# Display_Buttons.net
KiCad netlist of a schematic drawn in Altium Designer
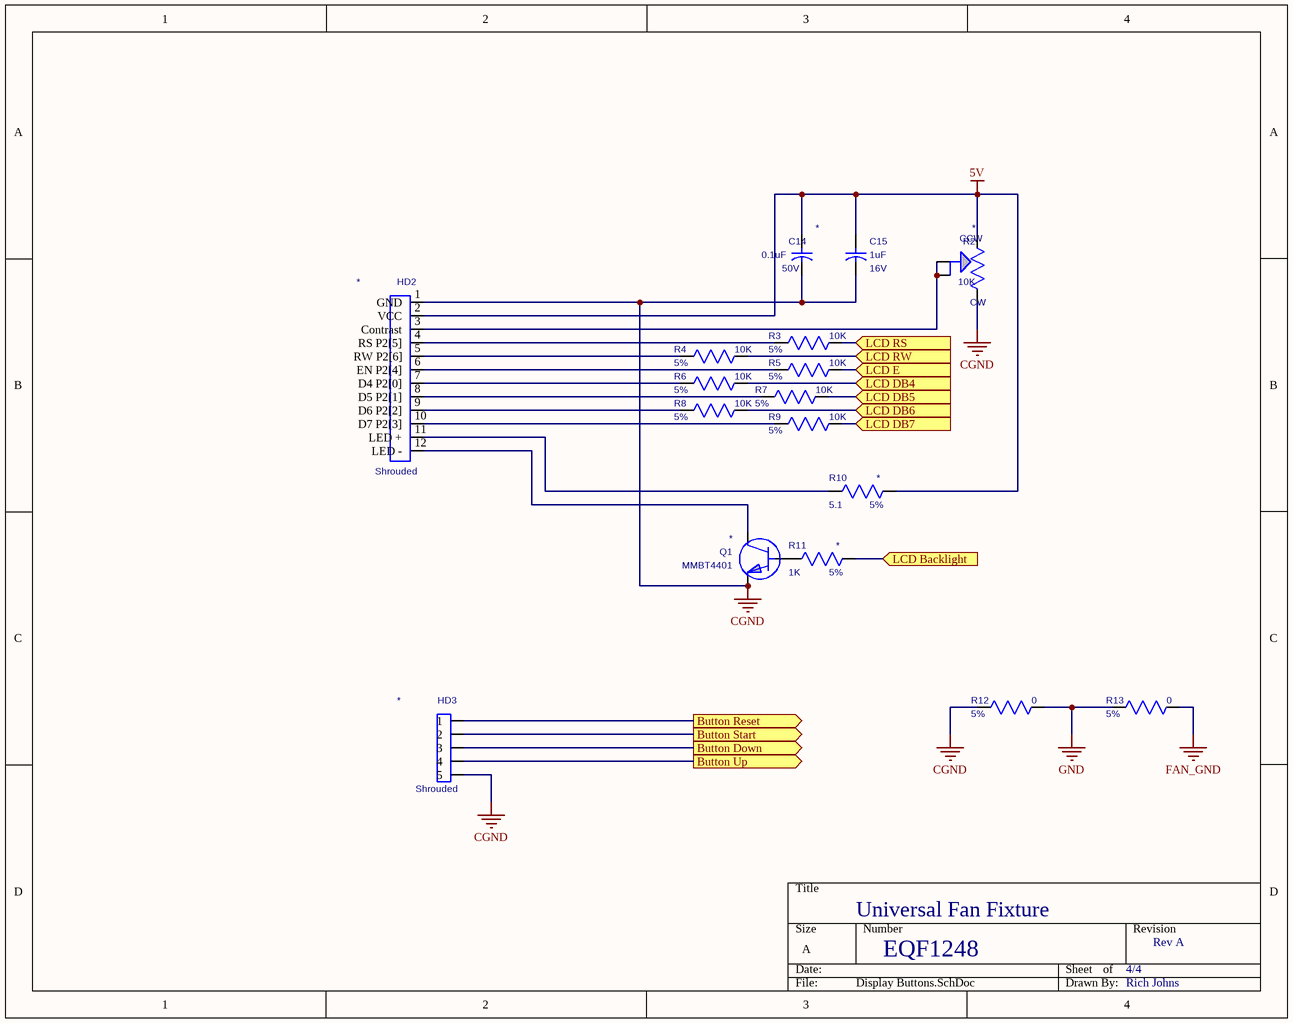
[diagram p0: Display Buttons.SchDoc]

(export (version "E")
  (design (tool "Eeschema 10.0.6"))
  (components
    (comp (ref "C14")
      (value "0.1uF")
      (footprint "0603")
      (fields
        (field (name "DNS") "*")
        (field (name "VOLTAGE") "50V")
        (field (name "TOLERANCE") "+/- 20%")
        (field (name "Comment") "CAP_NON_POLAR_SMT")
        (field (name "CHECKEDBY") "Sam Rhoufiry")
        (field (name "CREATEDBY") "Mike Tyger")
        (field (name "LASTUPDATEDBY") "Mike Tyger")
      )
      (libsource (lib "bome") (part "CAP_NON_POLAR_SMT"))
    )
    (comp (ref "C15")
      (value "1uF")
      (footprint "0603")
      (fields
        (field (name "TOLERANCE") "+/- 10%")
        (field (name "VOLTAGE") "16V")
        (field (name "Comment") "1.0uF_0603_16V")
        (field (name "CHECKEDBY") "gdeguzman")
        (field (name "LASTUPDATEDBY") "Rui Zhang")
      )
      (libsource (lib "bome") (part "1.0uF_0603_16V"))
    )
    (comp (ref "HD2")
      (value "HDR12PIN100SHRD")
      (footprint "HDR12PIN100SHRD")
      (description "Header, 0.1 in., 12 pins Pins, Shrouded, AMP: 1-64486-2")
      (fields
        (field (name "DNS") "*")
        (field (name "HEADERTYPE") "Shrouded")
        (field (name "CHECKEDBY") "Michael Angeli")
      )
      (libsource (lib "bome") (part "HDR12PIN100SHRD"))
    )
    (comp (ref "HD3")
      (value "HDR5PIN100SHRD")
      (footprint "HDR5PIN100SHRD")
      (description "Header, 0.100 in., 5 pin Pins, Shrouded, AMP: 644486-5")
      (fields
        (field (name "DNS") "*")
        (field (name "HEADERTYPE") "Shrouded")
        (field (name "CHECKEDBY") "Michael Angeli")
      )
      (libsource (lib "bome") (part "HDR5PIN100SHRD"))
    )
    (comp (ref "Q1")
      (value "MMBT4401")
      (footprint "SOT23-3")
      (description "Transistor, MMBT4401, 40V, SOT23-3, 500mA, NPN, Transistor, On Semi: MMBT4401LT1")
      (fields
        (field (name "DNS") "*")
        (field (name "VOLTAGE") "40V")
        (field (name "Comment") "NPN_TRANSISTOR")
        (field (name "CHECKEDBY") "gdeguzman")
        (field (name "CREATEDBY") "Mike Tyger")
        (field (name "LASTUPDATEDBY") "Mike Tyger")
      )
      (libsource (lib "bome") (part "NPN_TRANSISTOR"))
    )
    (comp (ref "R2")
      (value "10K")
      (footprint "6MM POT")
      (description "Resistor, 10K, Carbon, 20%, 0.2 in X 0.1 in or 0.2 in X 0.2 in, 0.1W, Panasonic: EVN-D8AA03B14")
      (fields
        (field (name "TOLERANCE") "20%")
        (field (name "DNS") "*")
        (field (name "Comment") "POT 6MM 10K")
        (field (name "CHECKEDBY") "B. Lyon")
      )
      (libsource (lib "bome") (part "POT 6MM 10K"))
    )
    (comp (ref "R3")
      (value "10K")
      (footprint "0603")
      (description "Resistor, 10K, ThickFilm, 5%, 0603, 1/10W, 2, Any")
      (fields
        (field (name "TOLERANCE") "5%")
        (field (name "Comment") "Resistor_0603_5%")
        (field (name "CHECKEDBY") "Joe Diffie")
        (field (name "LASTUPDATEDBY") "Rui Zhang")
      )
      (libsource (lib "bome") (part "Resistor_0603_5%"))
    )
    (comp (ref "R4")
      (value "10K")
      (footprint "0603")
      (description "Resistor, 10K, ThickFilm, 5%, 0603, 1/10W, 2, Any")
      (fields
        (field (name "TOLERANCE") "5%")
        (field (name "Comment") "Resistor_0603_5%")
        (field (name "CHECKEDBY") "Joe Diffie")
        (field (name "LASTUPDATEDBY") "Rui Zhang")
      )
      (libsource (lib "bome") (part "Resistor_0603_5%"))
    )
    (comp (ref "R5")
      (value "10K")
      (footprint "0603")
      (description "Resistor, 10K, ThickFilm, 5%, 0603, 1/10W, 2, Any")
      (fields
        (field (name "TOLERANCE") "5%")
        (field (name "Comment") "Resistor_0603_5%")
        (field (name "CHECKEDBY") "Joe Diffie")
        (field (name "LASTUPDATEDBY") "Rui Zhang")
      )
      (libsource (lib "bome") (part "Resistor_0603_5%"))
    )
    (comp (ref "R6")
      (value "10K")
      (footprint "0603")
      (description "Resistor, 10K, ThickFilm, 5%, 0603, 1/10W, 2, Any")
      (fields
        (field (name "TOLERANCE") "5%")
        (field (name "Comment") "Resistor_0603_5%")
        (field (name "CHECKEDBY") "Joe Diffie")
        (field (name "LASTUPDATEDBY") "Rui Zhang")
      )
      (libsource (lib "bome") (part "Resistor_0603_5%"))
    )
    (comp (ref "R7")
      (value "10K")
      (footprint "0603")
      (description "Resistor, 10K, ThickFilm, 5%, 0603, 1/10W, 2, Any")
      (fields
        (field (name "TOLERANCE") "5%")
        (field (name "Comment") "Resistor_0603_5%")
        (field (name "CHECKEDBY") "Joe Diffie")
        (field (name "LASTUPDATEDBY") "Rui Zhang")
      )
      (libsource (lib "bome") (part "Resistor_0603_5%"))
    )
    (comp (ref "R8")
      (value "10K")
      (footprint "0603")
      (description "Resistor, 10K, ThickFilm, 5%, 0603, 1/10W, 2, Any")
      (fields
        (field (name "TOLERANCE") "5%")
        (field (name "Comment") "Resistor_0603_5%")
        (field (name "CHECKEDBY") "Joe Diffie")
        (field (name "LASTUPDATEDBY") "Rui Zhang")
      )
      (libsource (lib "bome") (part "Resistor_0603_5%"))
    )
    (comp (ref "R9")
      (value "10K")
      (footprint "0603")
      (description "Resistor, 10K, ThickFilm, 5%, 0603, 1/10W, 2, Any")
      (fields
        (field (name "TOLERANCE") "5%")
        (field (name "Comment") "Resistor_0603_5%")
        (field (name "CHECKEDBY") "Joe Diffie")
        (field (name "LASTUPDATEDBY") "Rui Zhang")
      )
      (libsource (lib "bome") (part "Resistor_0603_5%"))
    )
    (comp (ref "R10")
      (value "5.1")
      (footprint "RC0603REFLOW-IPC")
      (description "Resistor, 5.1, ThickFilm, 5%, 0603, 1/10W, Any")
      (fields
        (field (name "DNS") "*")
        (field (name "TOLERANCE") "5%")
        (field (name "Comment") "R0603REFLOW_5%")
        (field (name "CHECKEDBY") "Michael Angeli")
      )
      (libsource (lib "bome") (part "R0603REFLOW_5%"))
    )
    (comp (ref "R11")
      (value "1K")
      (footprint "RC0603REFLOW-IPC")
      (description "Resistor, 1K, ThickFilm, 5%, 0603, 1/10W, Any")
      (fields
        (field (name "DNS") "*")
        (field (name "TOLERANCE") "5%")
        (field (name "Comment") "R0603REFLOW_5%")
        (field (name "CHECKEDBY") "Michael Angeli")
      )
      (libsource (lib "bome") (part "R0603REFLOW_5%"))
    )
    (comp (ref "R12")
      (value "0")
      (footprint "0603")
      (description "Resistor, 0, ThickFilm, 5%, 0603, 1/10W, 2, Any")
      (fields
        (field (name "TOLERANCE") "5%")
        (field (name "Comment") "Resistor_0603_5%")
        (field (name "CHECKEDBY") "Joe Diffie")
        (field (name "LASTUPDATEDBY") "Rui Zhang")
      )
      (libsource (lib "bome") (part "Resistor_0603_5%"))
    )
    (comp (ref "R13")
      (value "0")
      (footprint "0603")
      (description "Resistor, 0, ThickFilm, 5%, 0603, 1/10W, 2, Any")
      (fields
        (field (name "TOLERANCE") "5%")
        (field (name "Comment") "Resistor_0603_5%")
        (field (name "CHECKEDBY") "Joe Diffie")
        (field (name "LASTUPDATEDBY") "Rui Zhang")
      )
      (libsource (lib "bome") (part "Resistor_0603_5%"))
    )
  )
  (nets
    (net (code "1") (name "/Button Down") (class "Default")
      (node (ref "HD3") (pin "3") (pinfunction "3_3") (pintype "passive"))
    )
    (net (code "2") (name "/Button Reset") (class "Default")
      (node (ref "HD3") (pin "1") (pinfunction "1_1") (pintype "passive"))
    )
    (net (code "3") (name "/Button Start") (class "Default")
      (node (ref "HD3") (pin "2") (pinfunction "2_2") (pintype "passive"))
    )
    (net (code "4") (name "/Button Up") (class "Default")
      (node (ref "HD3") (pin "4") (pinfunction "4_4") (pintype "passive"))
    )
    (net (code "5") (name "/LCD Backlight") (class "Default")
      (node (ref "R11") (pin "1") (pinfunction "pin1_1") (pintype "passive"))
    )
    (net (code "6") (name "/LCD DB4") (class "Default")
      (node (ref "R6") (pin "1") (pinfunction "pin1_1") (pintype "passive"))
    )
    (net (code "7") (name "/LCD DB5") (class "Default")
      (node (ref "R7") (pin "1") (pinfunction "pin1_1") (pintype "passive"))
    )
    (net (code "8") (name "/LCD DB6") (class "Default")
      (node (ref "R8") (pin "1") (pinfunction "pin1_1") (pintype "passive"))
    )
    (net (code "9") (name "/LCD DB7") (class "Default")
      (node (ref "R9") (pin "1") (pinfunction "pin1_1") (pintype "passive"))
    )
    (net (code "10") (name "/LCD E") (class "Default")
      (node (ref "R5") (pin "1") (pinfunction "pin1_1") (pintype "passive"))
    )
    (net (code "11") (name "/LCD RS") (class "Default")
      (node (ref "R3") (pin "1") (pinfunction "pin1_1") (pintype "passive"))
    )
    (net (code "12") (name "/LCD RW") (class "Default")
      (node (ref "R4") (pin "1") (pinfunction "pin1_1") (pintype "passive"))
    )
    (net (code "13") (name "5V") (class "Default")
      (node (ref "C14") (pin "1") (pinfunction "pin1_1") (pintype "passive"))
      (node (ref "C15") (pin "1") (pinfunction "pin1_1") (pintype "passive"))
      (node (ref "HD2") (pin "2") (pinfunction "VCC_2") (pintype "passive"))
      (node (ref "R10") (pin "1") (pinfunction "pin1_1") (pintype "passive"))
      (node (ref "R2") (pin "1") (pinfunction "1_1") (pintype "passive"))
    )
    (net (code "14") (name "CGND") (class "Default")
      (node (ref "C14") (pin "2") (pinfunction "pin2_2") (pintype "passive"))
      (node (ref "C15") (pin "2") (pinfunction "pin2_2") (pintype "passive"))
      (node (ref "HD2") (pin "1") (pinfunction "GND_1") (pintype "passive"))
      (node (ref "HD3") (pin "5") (pinfunction "5_5") (pintype "passive"))
      (node (ref "Q1") (pin "2") (pinfunction "emitter_2") (pintype "passive"))
      (node (ref "R12") (pin "2") (pinfunction "pin2_2") (pintype "passive"))
      (node (ref "R2") (pin "4") (pinfunction "1_4") (pintype "passive"))
    )
    (net (code "15") (name "FAN_GND") (class "Default")
      (node (ref "R13") (pin "1") (pinfunction "pin1_1") (pintype "passive"))
    )
    (net (code "16") (name "GND") (class "Default")
      (node (ref "R12") (pin "1") (pinfunction "pin1_1") (pintype "passive"))
      (node (ref "R13") (pin "2") (pinfunction "pin2_2") (pintype "passive"))
    )
    (net (code "17") (name "Net-(HD2-Contrast)") (class "Default")
      (node (ref "HD2") (pin "3") (pinfunction "Contrast_3") (pintype "passive"))
      (node (ref "R2") (pin "2") (pinfunction "1_2") (pintype "passive"))
      (node (ref "R2") (pin "3") (pinfunction "1_3") (pintype "passive"))
    )
    (net (code "18") (name "Net-(HD2-D4_P2[0])") (class "Default")
      (node (ref "HD2") (pin "7") (pinfunction "D4_P2[0]_7") (pintype "passive"))
      (node (ref "R6") (pin "2") (pinfunction "pin2_2") (pintype "passive"))
    )
    (net (code "19") (name "Net-(HD2-D5_P2[1])") (class "Default")
      (node (ref "HD2") (pin "8") (pinfunction "D5_P2[1]_8") (pintype "passive"))
      (node (ref "R7") (pin "2") (pinfunction "pin2_2") (pintype "passive"))
    )
    (net (code "20") (name "Net-(HD2-D6_P2[2])") (class "Default")
      (node (ref "HD2") (pin "9") (pinfunction "D6_P2[2]_9") (pintype "passive"))
      (node (ref "R8") (pin "2") (pinfunction "pin2_2") (pintype "passive"))
    )
    (net (code "21") (name "Net-(HD2-D7_P2[3])") (class "Default")
      (node (ref "HD2") (pin "10") (pinfunction "D7_P2[3]_10") (pintype "passive"))
      (node (ref "R9") (pin "2") (pinfunction "pin2_2") (pintype "passive"))
    )
    (net (code "22") (name "Net-(HD2-EN_P2[4])") (class "Default")
      (node (ref "HD2") (pin "6") (pinfunction "EN_P2[4]_6") (pintype "passive"))
      (node (ref "R5") (pin "2") (pinfunction "pin2_2") (pintype "passive"))
    )
    (net (code "23") (name "Net-(HD2-LED_+)") (class "Default")
      (node (ref "HD2") (pin "11") (pinfunction "LED_+_11") (pintype "passive"))
      (node (ref "R10") (pin "2") (pinfunction "pin2_2") (pintype "passive"))
    )
    (net (code "24") (name "Net-(HD2-LED_-)") (class "Default")
      (node (ref "HD2") (pin "12") (pinfunction "LED_-_12") (pintype "passive"))
      (node (ref "Q1") (pin "3") (pinfunction "collector_3") (pintype "passive"))
    )
    (net (code "25") (name "Net-(HD2-RS_P2[5])") (class "Default")
      (node (ref "HD2") (pin "4") (pinfunction "RS_P2[5]_4") (pintype "passive"))
      (node (ref "R3") (pin "2") (pinfunction "pin2_2") (pintype "passive"))
    )
    (net (code "26") (name "Net-(HD2-RW_P2[6])") (class "Default")
      (node (ref "HD2") (pin "5") (pinfunction "RW_P2[6]_5") (pintype "passive"))
      (node (ref "R4") (pin "2") (pinfunction "pin2_2") (pintype "passive"))
    )
    (net (code "27") (name "Net-(Q1-base)") (class "Default")
      (node (ref "Q1") (pin "1") (pinfunction "base_1") (pintype "passive"))
      (node (ref "R11") (pin "2") (pinfunction "pin2_2") (pintype "passive"))
    )
    (net (code "28") (name "unconnected-(HD2-Pad13)") (class "Default")
      (node (ref "HD2") (pin "13") (pintype "passive"))
    )
    (net (code "29") (name "unconnected-(HD3-Pad6)") (class "Default")
      (node (ref "HD3") (pin "6") (pintype "passive"))
    )
  )
)
